# sdo_to_quiic_qt.net
KiCad netlist of a schematic drawn in EAGLE
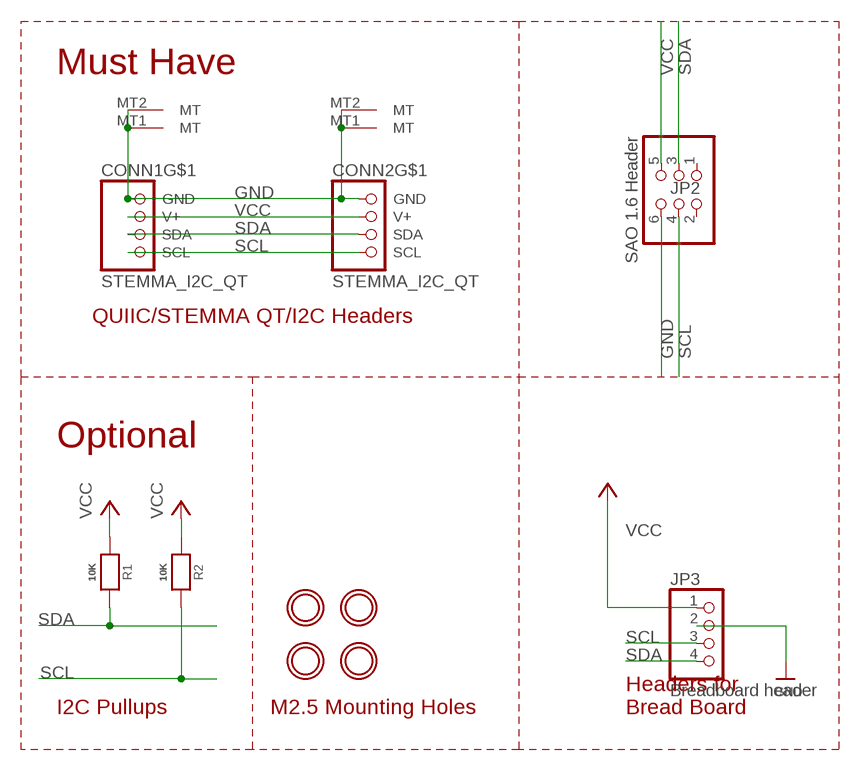
[diagram p0: schematic, sheet 1]

(export (version "E")
  (design (tool "Eeschema 10.0.6"))
  (components
    (comp (ref "CONN1")
      (value "STEMMA_I2C_QT")
      (footprint "eagle-import:JST_SH4")
      (libsource (lib "eagle-import") (part "STEMMA_I2C_QT"))
    )
    (comp (ref "CONN2")
      (value "STEMMA_I2C_QT")
      (footprint "eagle-import:JST_SH4")
      (libsource (lib "eagle-import") (part "STEMMA_I2C_QT"))
    )
    (comp (ref "JP2")
      (value "SAO 1.6 Header")
      (footprint "eagle-import:2X03_ROUND_70MIL")
      (libsource (lib "eagle-import") (part "HEADER-2X3"))
    )
    (comp (ref "JP3")
      (value "Breadboard header")
      (footprint "eagle-import:1X04_ROUND")
      (libsource (lib "eagle-import") (part "HEADER-1X4ROUND"))
    )
    (comp (ref "R1")
      (value "10K")
      (footprint "eagle-import:0805-NO")
      (libsource (lib "eagle-import") (part "RESISTOR0805_NOOUTLINE"))
    )
    (comp (ref "R2")
      (value "10K")
      (footprint "eagle-import:0805-NO")
      (libsource (lib "eagle-import") (part "RESISTOR0805_NOOUTLINE"))
    )
    (comp (ref "U$1")
      (value "MOUNTINGHOLE2.5")
      (footprint "eagle-import:MOUNTINGHOLE_2.5_PLATED")
      (libsource (lib "eagle-import") (part "MOUNTINGHOLE2.5"))
    )
    (comp (ref "U$17")
      (value "MOUNTINGHOLE2.5")
      (footprint "eagle-import:MOUNTINGHOLE_2.5_PLATED")
      (libsource (lib "eagle-import") (part "MOUNTINGHOLE2.5"))
    )
    (comp (ref "U$19")
      (value "MOUNTINGHOLE2.5")
      (footprint "eagle-import:MOUNTINGHOLE_2.5_PLATED")
      (libsource (lib "eagle-import") (part "MOUNTINGHOLE2.5"))
    )
    (comp (ref "U$21")
      (value "MOUNTINGHOLE2.5")
      (footprint "eagle-import:MOUNTINGHOLE_2.5_PLATED")
      (libsource (lib "eagle-import") (part "MOUNTINGHOLE2.5"))
    )
  )
  (nets
    (net (code "1") (name "/SCL") (class "Default")
      (node (ref "CONN1") (pin "4") (pinfunction "SCL_4") (pintype "passive"))
      (node (ref "CONN2") (pin "4") (pinfunction "SCL_4") (pintype "passive"))
      (node (ref "JP2") (pin "4") (pinfunction "4_4") (pintype "passive"))
      (node (ref "JP3") (pin "3") (pinfunction "3_3") (pintype "passive"))
      (node (ref "R2") (pin "2") (pinfunction "2_2") (pintype "passive"))
    )
    (net (code "2") (name "/SDA") (class "Default")
      (node (ref "CONN1") (pin "3") (pinfunction "SDA_3") (pintype "passive"))
      (node (ref "CONN2") (pin "3") (pinfunction "SDA_3") (pintype "passive"))
      (node (ref "JP2") (pin "3") (pinfunction "3_3") (pintype "passive"))
      (node (ref "JP3") (pin "4") (pinfunction "4_4") (pintype "passive"))
      (node (ref "R1") (pin "2") (pinfunction "2_2") (pintype "passive"))
    )
    (net (code "3") (name "GND") (class "Default")
      (node (ref "CONN1") (pin "1") (pinfunction "GND_1") (pintype "passive"))
      (node (ref "CONN1") (pin "MT1") (pinfunction "MT_MT1") (pintype "bidirectional"))
      (node (ref "CONN1") (pin "MT2") (pinfunction "MT_MT2") (pintype "bidirectional"))
      (node (ref "CONN2") (pin "1") (pinfunction "GND_1") (pintype "passive"))
      (node (ref "CONN2") (pin "MT1") (pinfunction "MT_MT1") (pintype "bidirectional"))
      (node (ref "CONN2") (pin "MT2") (pinfunction "MT_MT2") (pintype "bidirectional"))
      (node (ref "JP2") (pin "6") (pinfunction "6_6") (pintype "passive"))
      (node (ref "JP3") (pin "2") (pinfunction "2_2") (pintype "passive"))
    )
    (net (code "4") (name "VCC") (class "Default")
      (node (ref "CONN1") (pin "2") (pinfunction "V+_2") (pintype "passive"))
      (node (ref "CONN2") (pin "2") (pinfunction "V+_2") (pintype "passive"))
      (node (ref "JP2") (pin "5") (pinfunction "5_5") (pintype "passive"))
      (node (ref "JP3") (pin "1") (pinfunction "1_1") (pintype "passive"))
      (node (ref "R1") (pin "1") (pinfunction "1_1") (pintype "passive"))
      (node (ref "R2") (pin "1") (pinfunction "1_1") (pintype "passive"))
    )
    (net (code "5") (name "unconnected-(JP2-Pad1)") (class "Default")
      (node (ref "JP2") (pin "1") (pinfunction "1_1") (pintype "passive"))
    )
    (net (code "6") (name "unconnected-(JP2-Pad2)") (class "Default")
      (node (ref "JP2") (pin "2") (pinfunction "2_2") (pintype "passive"))
    )
  )
)
